# WS2812.net
KiCad netlist of a schematic drawn in Altium Designer
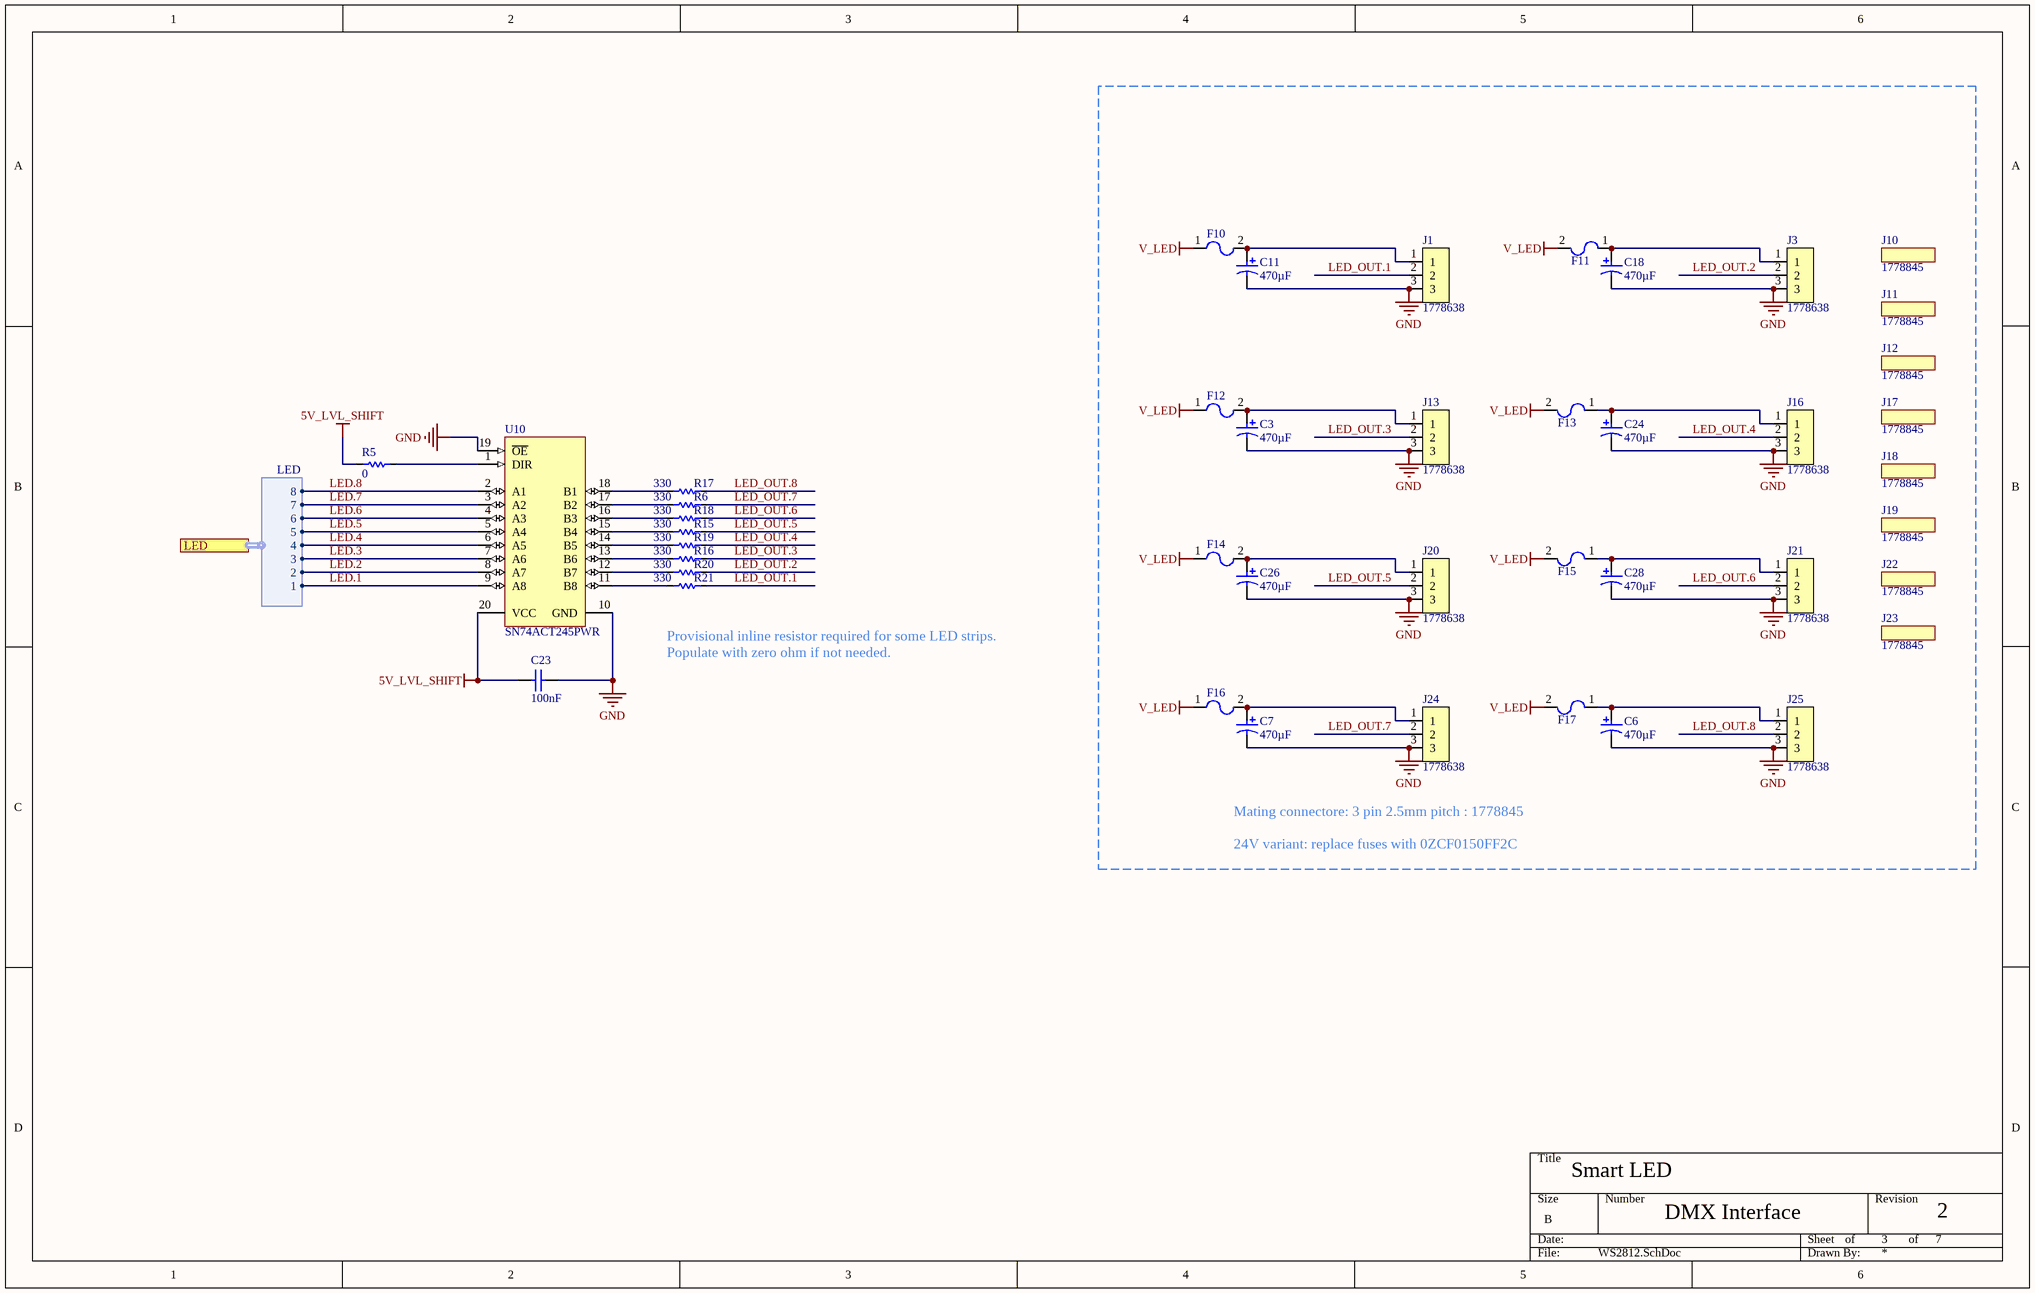
[diagram p0: WS2812.SchDoc]

(export (version "E")
  (design (tool "Eeschema 10.0.6"))
  (components
    (comp (ref "C3")
      (value "470µF")
      (footprint "CAP_POL_DIAM10_H22_SPACING5")
      (description "CAP ALUM 470UF 20% 50V RADIAL TH")
      (fields (field (name "TOLERANCE") "20%") (field (name "Comment") "REH1020471M050K"))
      (libsource (lib "Equus Computer Systems") (part "CAP-P-2"))
    )
    (comp (ref "C6")
      (value "470µF")
      (footprint "CAP_POL_DIAM10_H22_SPACING5")
      (description "CAP ALUM 470UF 20% 50V RADIAL TH")
      (fields (field (name "TOLERANCE") "20%") (field (name "Comment") "REH1020471M050K"))
      (libsource (lib "") (part "CAP-P-2_1"))
    )
    (comp (ref "C7")
      (value "470µF")
      (footprint "CAP_POL_DIAM10_H22_SPACING5")
      (description "CAP ALUM 470UF 20% 50V RADIAL TH")
      (fields (field (name "TOLERANCE") "20%") (field (name "Comment") "REH1020471M050K"))
      (libsource (lib "Equus Computer Systems") (part "CAP-P-2"))
    )
    (comp (ref "C11")
      (value "470µF")
      (footprint "CAP_POL_DIAM10_H22_SPACING5")
      (description "CAP ALUM 470UF 20% 50V RADIAL TH")
      (fields (field (name "TOLERANCE") "20%") (field (name "Comment") "REH1020471M050K"))
      (libsource (lib "Equus Computer Systems") (part "CAP-P-2"))
    )
    (comp (ref "C18")
      (value "470µF")
      (footprint "CAP_POL_DIAM10_H22_SPACING5")
      (description "CAP ALUM 470UF 20% 50V RADIAL TH")
      (fields (field (name "TOLERANCE") "20%") (field (name "Comment") "REH1020471M050K"))
      (libsource (lib "") (part "CAP-P-2_1"))
    )
    (comp (ref "C23")
      (value "100nF")
      (footprint "CAPC1608X10N_0603_MED")
      (fields (field (name "Comment") "CC0603KRX7R0BB104"))
      (libsource (lib "Equus Computer Systems") (part "CAP-NP-2"))
    )
    (comp (ref "C24")
      (value "470µF")
      (footprint "CAP_POL_DIAM10_H22_SPACING5")
      (description "CAP ALUM 470UF 20% 50V RADIAL TH")
      (fields (field (name "TOLERANCE") "20%") (field (name "Comment") "REH1020471M050K"))
      (libsource (lib "") (part "CAP-P-2_1"))
    )
    (comp (ref "C26")
      (value "470µF")
      (footprint "CAP_POL_DIAM10_H22_SPACING5")
      (description "CAP ALUM 470UF 20% 50V RADIAL TH")
      (fields (field (name "TOLERANCE") "20%") (field (name "Comment") "REH1020471M050K"))
      (libsource (lib "Equus Computer Systems") (part "CAP-P-2"))
    )
    (comp (ref "C28")
      (value "470µF")
      (footprint "CAP_POL_DIAM10_H22_SPACING5")
      (description "CAP ALUM 470UF 20% 50V RADIAL TH")
      (fields (field (name "TOLERANCE") "20%") (field (name "Comment") "REH1020471M050K"))
      (libsource (lib "") (part "CAP-P-2_1"))
    )
    (comp (ref "F10")
      (value "0ZCF0300BF2C")
      (footprint "0ZCF0300BF2C-Footprint-1")
      (description "Polymeric PTC Resettable Fuse 24V 3 A Ih Surface Mount 2920 (7351 Metric), Conca")
      (libsource (lib "") (part "Fuse_1"))
    )
    (comp (ref "F11")
      (value "0ZCF0300BF2C")
      (footprint "0ZCF0300BF2C-Footprint-1")
      (description "Polymeric PTC Resettable Fuse 24V 3 A Ih Surface Mount 2920 (7351 Metric), Conca")
      (libsource (lib "Equus Computer Systems") (part "Fuse"))
    )
    (comp (ref "F12")
      (value "0ZCF0300BF2C")
      (footprint "0ZCF0300BF2C-Footprint-1")
      (description "Polymeric PTC Resettable Fuse 24V 3 A Ih Surface Mount 2920 (7351 Metric), Conca")
      (libsource (lib "") (part "Fuse_1"))
    )
    (comp (ref "F13")
      (value "0ZCF0300BF2C")
      (footprint "0ZCF0300BF2C-Footprint-1")
      (description "Polymeric PTC Resettable Fuse 24V 3 A Ih Surface Mount 2920 (7351 Metric), Conca")
      (libsource (lib "Equus Computer Systems") (part "Fuse"))
    )
    (comp (ref "F14")
      (value "0ZCF0300BF2C")
      (footprint "0ZCF0300BF2C-Footprint-1")
      (description "Polymeric PTC Resettable Fuse 24V 3 A Ih Surface Mount 2920 (7351 Metric), Conca")
      (libsource (lib "") (part "Fuse_1"))
    )
    (comp (ref "F15")
      (value "0ZCF0300BF2C")
      (footprint "0ZCF0300BF2C-Footprint-1")
      (description "Polymeric PTC Resettable Fuse 24V 3 A Ih Surface Mount 2920 (7351 Metric), Conca")
      (libsource (lib "Equus Computer Systems") (part "Fuse"))
    )
    (comp (ref "F16")
      (value "0ZCF0300BF2C")
      (footprint "0ZCF0300BF2C-Footprint-1")
      (description "Polymeric PTC Resettable Fuse 24V 3 A Ih Surface Mount 2920 (7351 Metric), Conca")
      (libsource (lib "") (part "Fuse_1"))
    )
    (comp (ref "F17")
      (value "0ZCF0300BF2C")
      (footprint "0ZCF0300BF2C-Footprint-1")
      (description "Polymeric PTC Resettable Fuse 24V 3 A Ih Surface Mount 2920 (7351 Metric), Conca")
      (libsource (lib "Equus Computer Systems") (part "Fuse"))
    )
    (comp (ref "J1")
      (value "1778638")
      (footprint "1778638-Footprint-1")
      (description "Terminal Block, Header, R/A, 3Way, Th;")
      (libsource (lib "Equus Computer Systems") (part "HEADER-3x1"))
    )
    (comp (ref "J3")
      (value "1778638")
      (footprint "1778638-Footprint-1")
      (description "Terminal Block, Header, R/A, 3Way, Th;")
      (libsource (lib "Equus Computer Systems") (part "HEADER-3x1"))
    )
    (comp (ref "J10")
      (value "1778845")
      (footprint "1778845-Footprint-1")
      (description "Terminal Block Connector; Plug; Mini; Spring Cage; 3; 2.5 mm; 26-20 AWG; 5 A; 150 V")
      (libsource (lib "Equus Computer Systems") (part "MatingPartForBom"))
    )
    (comp (ref "J11")
      (value "1778845")
      (footprint "1778845-Footprint-1")
      (description "Terminal Block Connector; Plug; Mini; Spring Cage; 3; 2.5 mm; 26-20 AWG; 5 A; 150 V")
      (libsource (lib "Equus Computer Systems") (part "MatingPartForBom"))
    )
    (comp (ref "J12")
      (value "1778845")
      (footprint "1778845-Footprint-1")
      (description "Terminal Block Connector; Plug; Mini; Spring Cage; 3; 2.5 mm; 26-20 AWG; 5 A; 150 V")
      (libsource (lib "Equus Computer Systems") (part "MatingPartForBom"))
    )
    (comp (ref "J13")
      (value "1778638")
      (footprint "1778638-Footprint-1")
      (description "Terminal Block, Header, R/A, 3Way, Th;")
      (libsource (lib "Equus Computer Systems") (part "HEADER-3x1"))
    )
    (comp (ref "J16")
      (value "1778638")
      (footprint "1778638-Footprint-1")
      (description "Terminal Block, Header, R/A, 3Way, Th;")
      (libsource (lib "Equus Computer Systems") (part "HEADER-3x1"))
    )
    (comp (ref "J17")
      (value "1778845")
      (footprint "1778845-Footprint-1")
      (description "Terminal Block Connector; Plug; Mini; Spring Cage; 3; 2.5 mm; 26-20 AWG; 5 A; 150 V")
      (libsource (lib "Equus Computer Systems") (part "MatingPartForBom"))
    )
    (comp (ref "J18")
      (value "1778845")
      (footprint "1778845-Footprint-1")
      (description "Terminal Block Connector; Plug; Mini; Spring Cage; 3; 2.5 mm; 26-20 AWG; 5 A; 150 V")
      (libsource (lib "Equus Computer Systems") (part "MatingPartForBom"))
    )
    (comp (ref "J19")
      (value "1778845")
      (footprint "1778845-Footprint-1")
      (description "Terminal Block Connector; Plug; Mini; Spring Cage; 3; 2.5 mm; 26-20 AWG; 5 A; 150 V")
      (libsource (lib "Equus Computer Systems") (part "MatingPartForBom"))
    )
    (comp (ref "J20")
      (value "1778638")
      (footprint "1778638-Footprint-1")
      (description "Terminal Block, Header, R/A, 3Way, Th;")
      (libsource (lib "Equus Computer Systems") (part "HEADER-3x1"))
    )
    (comp (ref "J21")
      (value "1778638")
      (footprint "1778638-Footprint-1")
      (description "Terminal Block, Header, R/A, 3Way, Th;")
      (libsource (lib "Equus Computer Systems") (part "HEADER-3x1"))
    )
    (comp (ref "J22")
      (value "1778845")
      (footprint "1778845-Footprint-1")
      (description "Terminal Block Connector; Plug; Mini; Spring Cage; 3; 2.5 mm; 26-20 AWG; 5 A; 150 V")
      (libsource (lib "Equus Computer Systems") (part "MatingPartForBom"))
    )
    (comp (ref "J23")
      (value "1778845")
      (footprint "1778845-Footprint-1")
      (description "Terminal Block Connector; Plug; Mini; Spring Cage; 3; 2.5 mm; 26-20 AWG; 5 A; 150 V")
      (libsource (lib "Equus Computer Systems") (part "MatingPartForBom"))
    )
    (comp (ref "J24")
      (value "1778638")
      (footprint "1778638-Footprint-1")
      (description "Terminal Block, Header, R/A, 3Way, Th;")
      (libsource (lib "Equus Computer Systems") (part "HEADER-3x1"))
    )
    (comp (ref "J25")
      (value "1778638")
      (footprint "1778638-Footprint-1")
      (description "Terminal Block, Header, R/A, 3Way, Th;")
      (libsource (lib "Equus Computer Systems") (part "HEADER-3x1"))
    )
    (comp (ref "R5")
      (value "0")
      (footprint "RESC1608X06N_0603_MED")
      (description "RC Series 0603 0.1 W 0 Ohm Jumper Surface Mount Thick Film Chip Resistor")
      (fields (field (name "TOLERANCE") "1%") (field (name "POWER") "100mW"))
      (libsource (lib "Equus Computer Systems") (part "RES-2"))
    )
    (comp (ref "R6")
      (value "330")
      (footprint "RESC1608X06N_0603_MED")
      (fields
        (field (name "POWER") "100mW")
        (field (name "TOLERANCE") "1%")
        (field (name "Comment") "RC0603FR-07330RL")
      )
      (libsource (lib "Equus Computer Systems") (part "RES-2"))
    )
    (comp (ref "R15")
      (value "330")
      (footprint "RESC1608X06N_0603_MED")
      (fields
        (field (name "POWER") "100mW")
        (field (name "TOLERANCE") "1%")
        (field (name "Comment") "RC0603FR-07330RL")
      )
      (libsource (lib "Equus Computer Systems") (part "RES-2"))
    )
    (comp (ref "R16")
      (value "330")
      (footprint "RESC1608X06N_0603_MED")
      (fields
        (field (name "POWER") "100mW")
        (field (name "TOLERANCE") "1%")
        (field (name "Comment") "RC0603FR-07330RL")
      )
      (libsource (lib "Equus Computer Systems") (part "RES-2"))
    )
    (comp (ref "R17")
      (value "330")
      (footprint "RESC1608X06N_0603_MED")
      (fields
        (field (name "POWER") "100mW")
        (field (name "TOLERANCE") "1%")
        (field (name "Comment") "RC0603FR-07330RL")
      )
      (libsource (lib "Equus Computer Systems") (part "RES-2"))
    )
    (comp (ref "R18")
      (value "330")
      (footprint "RESC1608X06N_0603_MED")
      (fields
        (field (name "POWER") "100mW")
        (field (name "TOLERANCE") "1%")
        (field (name "Comment") "RC0603FR-07330RL")
      )
      (libsource (lib "Equus Computer Systems") (part "RES-2"))
    )
    (comp (ref "R19")
      (value "330")
      (footprint "RESC1608X06N_0603_MED")
      (fields
        (field (name "POWER") "100mW")
        (field (name "TOLERANCE") "1%")
        (field (name "Comment") "RC0603FR-07330RL")
      )
      (libsource (lib "Equus Computer Systems") (part "RES-2"))
    )
    (comp (ref "R20")
      (value "330")
      (footprint "RESC1608X06N_0603_MED")
      (fields
        (field (name "POWER") "100mW")
        (field (name "TOLERANCE") "1%")
        (field (name "Comment") "RC0603FR-07330RL")
      )
      (libsource (lib "Equus Computer Systems") (part "RES-2"))
    )
    (comp (ref "R21")
      (value "330")
      (footprint "RESC1608X06N_0603_MED")
      (fields
        (field (name "POWER") "100mW")
        (field (name "TOLERANCE") "1%")
        (field (name "Comment") "RC0603FR-07330RL")
      )
      (libsource (lib "Equus Computer Systems") (part "RES-2"))
    )
    (comp (ref "U10")
      (value "SN74ACT245PWR")
      (footprint "PW0020A_L")
      (description "Bus Transceiver, ACT Series, 1-Func, 8-Bit, True Output, CMOS, PDSO20")
      (libsource (lib "Equus Computer Systems") (part "TI-SN_CDX4XXXXXX245XX_6XXX-20"))
    )
  )
  (nets
    (net (code "2") (name "/LED.1") (class "Default")
      (node (ref "U10") (pin "9") (pinfunction "A8_9") (pintype "bidirectional"))
    )
    (net (code "3") (name "/LED.2") (class "Default")
      (node (ref "U10") (pin "8") (pinfunction "A7_8") (pintype "bidirectional"))
    )
    (net (code "4") (name "/LED.3") (class "Default")
      (node (ref "U10") (pin "7") (pinfunction "A6_7") (pintype "bidirectional"))
    )
    (net (code "5") (name "/LED.4") (class "Default")
      (node (ref "U10") (pin "6") (pinfunction "A5_6") (pintype "bidirectional"))
    )
    (net (code "6") (name "/LED.5") (class "Default")
      (node (ref "U10") (pin "5") (pinfunction "A4_5") (pintype "bidirectional"))
    )
    (net (code "7") (name "/LED.6") (class "Default")
      (node (ref "U10") (pin "4") (pinfunction "A3_4") (pintype "bidirectional"))
    )
    (net (code "8") (name "/LED.7") (class "Default")
      (node (ref "U10") (pin "3") (pinfunction "A2_3") (pintype "bidirectional"))
    )
    (net (code "9") (name "/LED.8") (class "Default")
      (node (ref "U10") (pin "2") (pinfunction "A1_2") (pintype "bidirectional"))
    )
    (net (code "10") (name "/LED_OUT.1") (class "Default")
      (node (ref "J1") (pin "2") (pinfunction "2_2") (pintype "passive"))
      (node (ref "R21") (pin "2") (pinfunction "2_2") (pintype "passive"))
    )
    (net (code "11") (name "/LED_OUT.2") (class "Default")
      (node (ref "J3") (pin "2") (pinfunction "2_2") (pintype "passive"))
      (node (ref "R20") (pin "2") (pinfunction "2_2") (pintype "passive"))
    )
    (net (code "12") (name "/LED_OUT.3") (class "Default")
      (node (ref "J13") (pin "2") (pinfunction "2_2") (pintype "passive"))
      (node (ref "R16") (pin "2") (pinfunction "2_2") (pintype "passive"))
    )
    (net (code "13") (name "/LED_OUT.4") (class "Default")
      (node (ref "J16") (pin "2") (pinfunction "2_2") (pintype "passive"))
      (node (ref "R19") (pin "2") (pinfunction "2_2") (pintype "passive"))
    )
    (net (code "14") (name "/LED_OUT.5") (class "Default")
      (node (ref "J20") (pin "2") (pinfunction "2_2") (pintype "passive"))
      (node (ref "R15") (pin "2") (pinfunction "2_2") (pintype "passive"))
    )
    (net (code "15") (name "/LED_OUT.6") (class "Default")
      (node (ref "J21") (pin "2") (pinfunction "2_2") (pintype "passive"))
      (node (ref "R18") (pin "2") (pinfunction "2_2") (pintype "passive"))
    )
    (net (code "16") (name "/LED_OUT.7") (class "Default")
      (node (ref "J24") (pin "2") (pinfunction "2_2") (pintype "passive"))
      (node (ref "R6") (pin "2") (pinfunction "2_2") (pintype "passive"))
    )
    (net (code "17") (name "/LED_OUT.8") (class "Default")
      (node (ref "J25") (pin "2") (pinfunction "2_2") (pintype "passive"))
      (node (ref "R17") (pin "2") (pinfunction "2_2") (pintype "passive"))
    )
    (net (code "19") (name "5V_LVL_SHIFT") (class "Default")
      (node (ref "C23") (pin "2") (pinfunction "2_2") (pintype "passive"))
      (node (ref "R5") (pin "2") (pinfunction "2_2") (pintype "passive"))
      (node (ref "U10") (pin "20") (pinfunction "VCC_20") (pintype "power_in"))
    )
    (net (code "20") (name "GND") (class "Default")
      (node (ref "C11") (pin "2") (pinfunction "2_2") (pintype "passive"))
      (node (ref "C18") (pin "2") (pinfunction "2_2") (pintype "passive"))
      (node (ref "C23") (pin "1") (pinfunction "1_1") (pintype "passive"))
      (node (ref "C24") (pin "2") (pinfunction "2_2") (pintype "passive"))
      (node (ref "C26") (pin "2") (pinfunction "2_2") (pintype "passive"))
      (node (ref "C28") (pin "2") (pinfunction "2_2") (pintype "passive"))
      (node (ref "C3") (pin "2") (pinfunction "2_2") (pintype "passive"))
      (node (ref "C6") (pin "2") (pinfunction "2_2") (pintype "passive"))
      (node (ref "C7") (pin "2") (pinfunction "2_2") (pintype "passive"))
      (node (ref "J1") (pin "3") (pinfunction "3_3") (pintype "passive"))
      (node (ref "J13") (pin "3") (pinfunction "3_3") (pintype "passive"))
      (node (ref "J16") (pin "3") (pinfunction "3_3") (pintype "passive"))
      (node (ref "J20") (pin "3") (pinfunction "3_3") (pintype "passive"))
      (node (ref "J21") (pin "3") (pinfunction "3_3") (pintype "passive"))
      (node (ref "J24") (pin "3") (pinfunction "3_3") (pintype "passive"))
      (node (ref "J25") (pin "3") (pinfunction "3_3") (pintype "passive"))
      (node (ref "J3") (pin "3") (pinfunction "3_3") (pintype "passive"))
      (node (ref "U10") (pin "10") (pinfunction "GND_10") (pintype "power_in"))
      (node (ref "U10") (pin "19") (pinfunction "~{OE}_19") (pintype "input"))
    )
    (net (code "21") (name "Net-(C3-Pad1)") (class "Default")
      (node (ref "C3") (pin "1") (pinfunction "1_1") (pintype "passive"))
      (node (ref "F12") (pin "2") (pinfunction "2_2") (pintype "passive"))
      (node (ref "J13") (pin "1") (pinfunction "1_1") (pintype "passive"))
    )
    (net (code "22") (name "Net-(C6-Pad1)") (class "Default")
      (node (ref "C6") (pin "1") (pinfunction "1_1") (pintype "passive"))
      (node (ref "F17") (pin "1") (pinfunction "1_1") (pintype "passive"))
      (node (ref "J25") (pin "1") (pinfunction "1_1") (pintype "passive"))
    )
    (net (code "23") (name "Net-(C7-Pad1)") (class "Default")
      (node (ref "C7") (pin "1") (pinfunction "1_1") (pintype "passive"))
      (node (ref "F16") (pin "2") (pinfunction "2_2") (pintype "passive"))
      (node (ref "J24") (pin "1") (pinfunction "1_1") (pintype "passive"))
    )
    (net (code "24") (name "Net-(C11-Pad1)") (class "Default")
      (node (ref "C11") (pin "1") (pinfunction "1_1") (pintype "passive"))
      (node (ref "F10") (pin "2") (pinfunction "2_2") (pintype "passive"))
      (node (ref "J1") (pin "1") (pinfunction "1_1") (pintype "passive"))
    )
    (net (code "25") (name "Net-(C18-Pad1)") (class "Default")
      (node (ref "C18") (pin "1") (pinfunction "1_1") (pintype "passive"))
      (node (ref "F11") (pin "1") (pinfunction "1_1") (pintype "passive"))
      (node (ref "J3") (pin "1") (pinfunction "1_1") (pintype "passive"))
    )
    (net (code "26") (name "Net-(C24-Pad1)") (class "Default")
      (node (ref "C24") (pin "1") (pinfunction "1_1") (pintype "passive"))
      (node (ref "F13") (pin "1") (pinfunction "1_1") (pintype "passive"))
      (node (ref "J16") (pin "1") (pinfunction "1_1") (pintype "passive"))
    )
    (net (code "27") (name "Net-(C26-Pad1)") (class "Default")
      (node (ref "C26") (pin "1") (pinfunction "1_1") (pintype "passive"))
      (node (ref "F14") (pin "2") (pinfunction "2_2") (pintype "passive"))
      (node (ref "J20") (pin "1") (pinfunction "1_1") (pintype "passive"))
    )
    (net (code "28") (name "Net-(C28-Pad1)") (class "Default")
      (node (ref "C28") (pin "1") (pinfunction "1_1") (pintype "passive"))
      (node (ref "F15") (pin "1") (pinfunction "1_1") (pintype "passive"))
      (node (ref "J21") (pin "1") (pinfunction "1_1") (pintype "passive"))
    )
    (net (code "29") (name "Net-(U10-B1)") (class "Default")
      (node (ref "R17") (pin "1") (pinfunction "1_1") (pintype "passive"))
      (node (ref "U10") (pin "18") (pinfunction "B1_18") (pintype "bidirectional"))
    )
    (net (code "30") (name "Net-(U10-B2)") (class "Default")
      (node (ref "R6") (pin "1") (pinfunction "1_1") (pintype "passive"))
      (node (ref "U10") (pin "17") (pinfunction "B2_17") (pintype "bidirectional"))
    )
    (net (code "31") (name "Net-(U10-B3)") (class "Default")
      (node (ref "R18") (pin "1") (pinfunction "1_1") (pintype "passive"))
      (node (ref "U10") (pin "16") (pinfunction "B3_16") (pintype "bidirectional"))
    )
    (net (code "32") (name "Net-(U10-B4)") (class "Default")
      (node (ref "R15") (pin "1") (pinfunction "1_1") (pintype "passive"))
      (node (ref "U10") (pin "15") (pinfunction "B4_15") (pintype "bidirectional"))
    )
    (net (code "33") (name "Net-(U10-B5)") (class "Default")
      (node (ref "R19") (pin "1") (pinfunction "1_1") (pintype "passive"))
      (node (ref "U10") (pin "14") (pinfunction "B5_14") (pintype "bidirectional"))
    )
    (net (code "34") (name "Net-(U10-B6)") (class "Default")
      (node (ref "R16") (pin "1") (pinfunction "1_1") (pintype "passive"))
      (node (ref "U10") (pin "13") (pinfunction "B6_13") (pintype "bidirectional"))
    )
    (net (code "35") (name "Net-(U10-B7)") (class "Default")
      (node (ref "R20") (pin "1") (pinfunction "1_1") (pintype "passive"))
      (node (ref "U10") (pin "12") (pinfunction "B7_12") (pintype "bidirectional"))
    )
    (net (code "36") (name "Net-(U10-B8)") (class "Default")
      (node (ref "R21") (pin "1") (pinfunction "1_1") (pintype "passive"))
      (node (ref "U10") (pin "11") (pinfunction "B8_11") (pintype "bidirectional"))
    )
    (net (code "37") (name "Net-(U10-DIR)") (class "Default")
      (node (ref "R5") (pin "1") (pinfunction "1_1") (pintype "passive"))
      (node (ref "U10") (pin "1") (pinfunction "DIR_1") (pintype "input"))
    )
    (net (code "38") (name "V_LED") (class "Default")
      (node (ref "F10") (pin "1") (pinfunction "1_1") (pintype "passive"))
      (node (ref "F11") (pin "2") (pinfunction "2_2") (pintype "passive"))
      (node (ref "F12") (pin "1") (pinfunction "1_1") (pintype "passive"))
      (node (ref "F13") (pin "2") (pinfunction "2_2") (pintype "passive"))
      (node (ref "F14") (pin "1") (pinfunction "1_1") (pintype "passive"))
      (node (ref "F15") (pin "2") (pinfunction "2_2") (pintype "passive"))
      (node (ref "F16") (pin "1") (pinfunction "1_1") (pintype "passive"))
      (node (ref "F17") (pin "2") (pinfunction "2_2") (pintype "passive"))
    )
  )
)
